# RJ45_Breakout.net
KiCad netlist of a schematic drawn in EAGLE
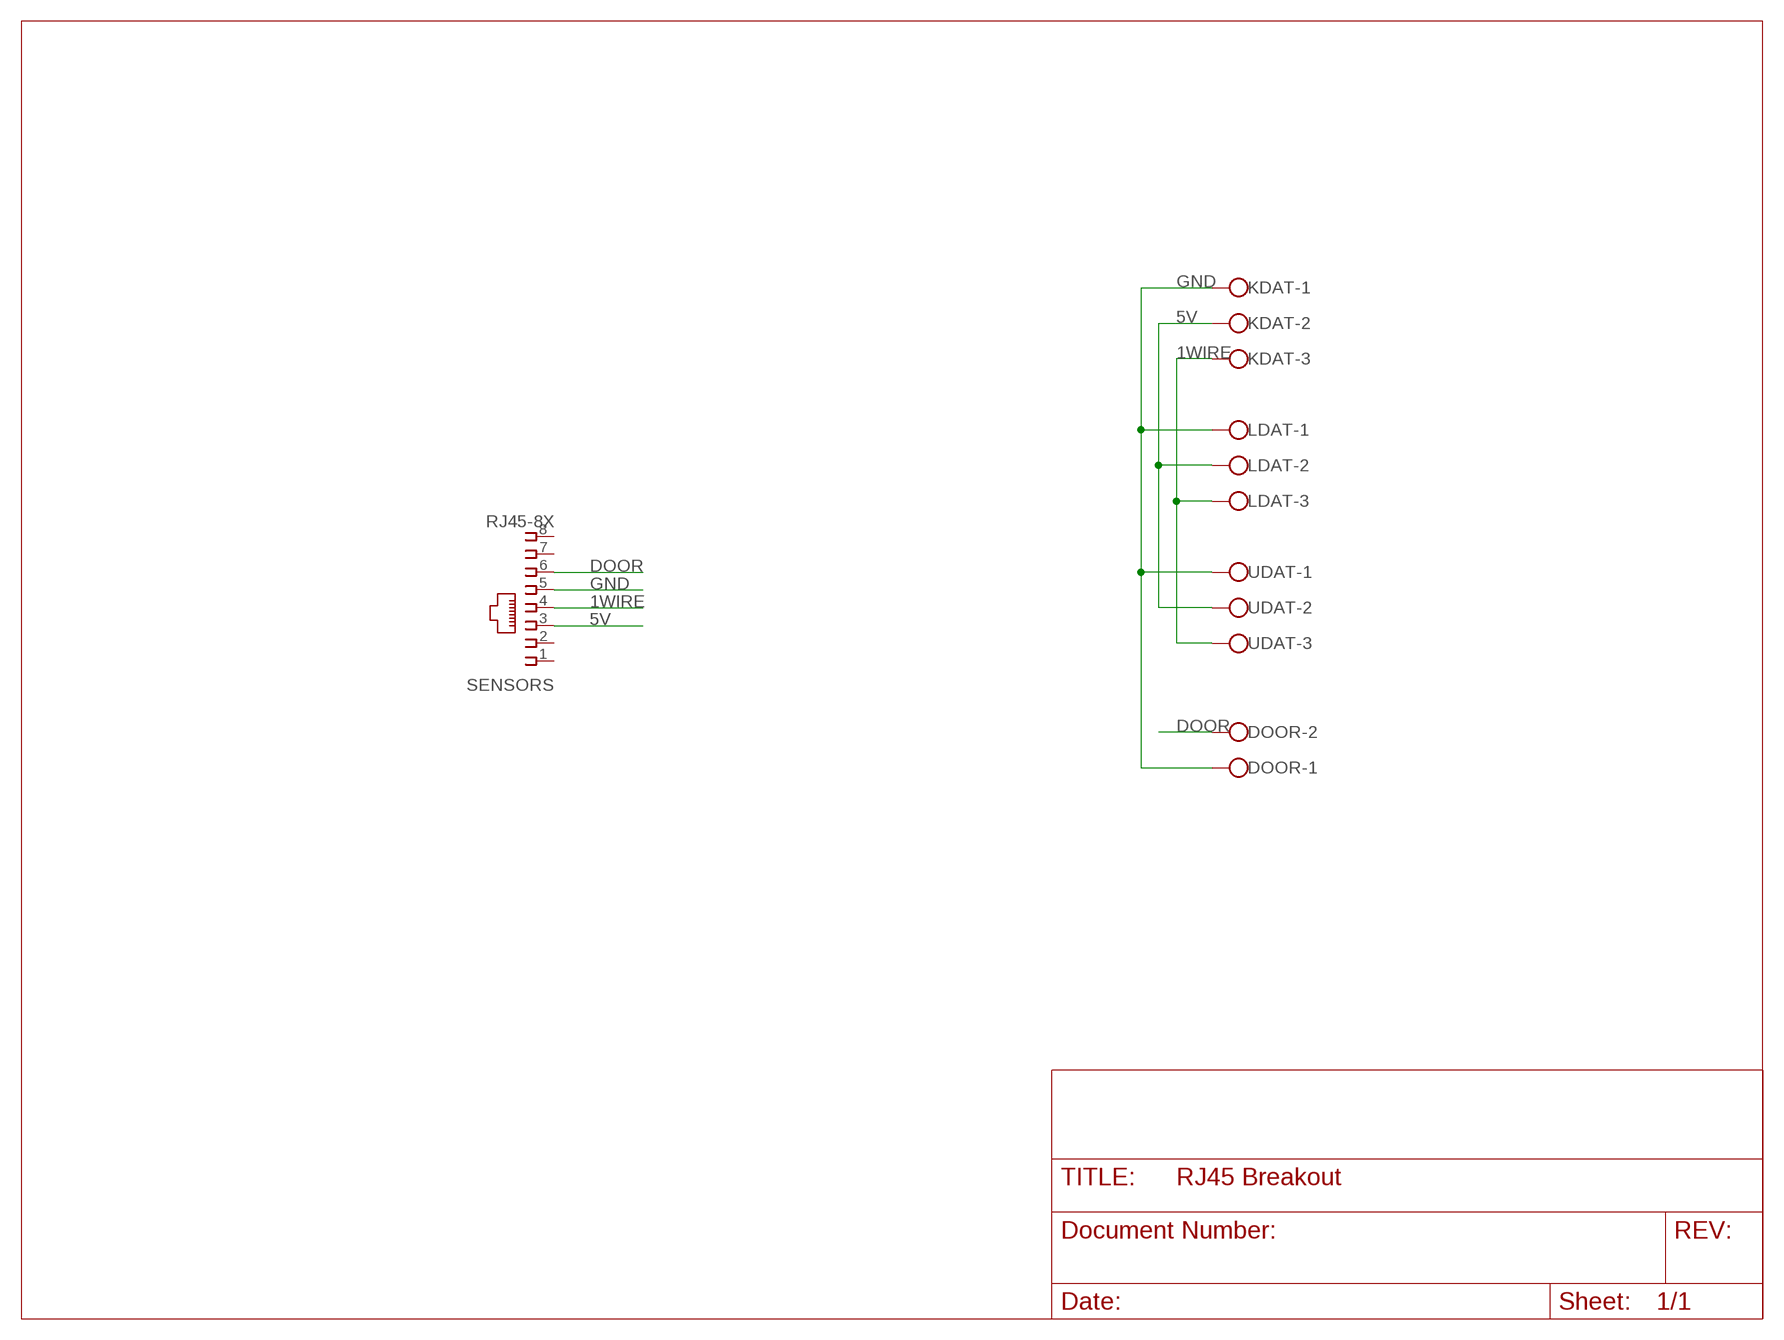
[diagram p0: schematic, sheet 1]

(export (version "E")
  (design (tool "Eeschema 10.0.6"))
  (components
    (comp (ref "DOOR")
      (value "W237-102")
      (footprint "eagle-import:W237-102")
      (fields (field (name "MPN") "237-102"))
      (libsource (lib "eagle-import") (part "W237-102"))
    )
    (comp (ref "KDAT")
      (value "W237-103")
      (footprint "eagle-import:W237-103")
      (fields (field (name "MPN") "237-103"))
      (libsource (lib "eagle-import") (part "W237-103"))
    )
    (comp (ref "LDAT")
      (value "W237-103")
      (footprint "eagle-import:W237-103")
      (fields (field (name "MPN") "237-103"))
      (libsource (lib "eagle-import") (part "W237-103"))
    )
    (comp (ref "SENSORS")
      (value "RJ45-8X")
      (footprint "eagle-import:RJ45-NO-SHIELD")
      (libsource (lib "eagle-import") (part "RJ45-8X"))
    )
    (comp (ref "UDAT")
      (value "W237-103")
      (footprint "eagle-import:W237-103")
      (fields (field (name "MPN") "237-103"))
      (libsource (lib "eagle-import") (part "W237-103"))
    )
  )
  (nets
    (net (code "1") (name "/1WIRE") (class "Default")
      (node (ref "KDAT") (pin "3") (pinfunction "KL_3") (pintype "passive"))
      (node (ref "LDAT") (pin "3") (pinfunction "KL_3") (pintype "passive"))
      (node (ref "SENSORS") (pin "4") (pinfunction "4_4") (pintype "passive"))
      (node (ref "UDAT") (pin "3") (pinfunction "KL_3") (pintype "passive"))
    )
    (net (code "2") (name "/5V") (class "Default")
      (node (ref "KDAT") (pin "2") (pinfunction "KL_2") (pintype "passive"))
      (node (ref "LDAT") (pin "2") (pinfunction "KL_2") (pintype "passive"))
      (node (ref "SENSORS") (pin "3") (pinfunction "3_3") (pintype "passive"))
      (node (ref "UDAT") (pin "2") (pinfunction "KL_2") (pintype "passive"))
    )
    (net (code "3") (name "/DOOR") (class "Default")
      (node (ref "DOOR") (pin "2") (pinfunction "KL_2") (pintype "passive"))
      (node (ref "SENSORS") (pin "6") (pinfunction "6_6") (pintype "passive"))
    )
    (net (code "4") (name "/GND") (class "Default")
      (node (ref "DOOR") (pin "1") (pinfunction "KL_1") (pintype "passive"))
      (node (ref "KDAT") (pin "1") (pinfunction "KL_1") (pintype "passive"))
      (node (ref "LDAT") (pin "1") (pinfunction "KL_1") (pintype "passive"))
      (node (ref "SENSORS") (pin "5") (pinfunction "5_5") (pintype "passive"))
      (node (ref "UDAT") (pin "1") (pinfunction "KL_1") (pintype "passive"))
    )
    (net (code "5") (name "unconnected-(SENSORS-Pad1)") (class "Default")
      (node (ref "SENSORS") (pin "1") (pinfunction "1_1") (pintype "passive"))
    )
    (net (code "6") (name "unconnected-(SENSORS-Pad2)") (class "Default")
      (node (ref "SENSORS") (pin "2") (pinfunction "2_2") (pintype "passive"))
    )
    (net (code "7") (name "unconnected-(SENSORS-Pad7)") (class "Default")
      (node (ref "SENSORS") (pin "7") (pinfunction "7_7") (pintype "passive"))
    )
    (net (code "8") (name "unconnected-(SENSORS-Pad8)") (class "Default")
      (node (ref "SENSORS") (pin "8") (pinfunction "8_8") (pintype "passive"))
    )
  )
)
